# crossfire-20x20.net
KiCad netlist of a schematic drawn in EAGLE
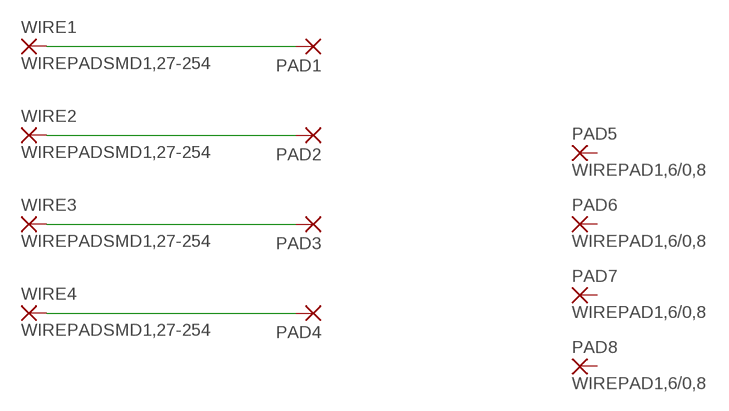
[diagram p0: schematic, sheet 1]

(export (version "E")
  (design (tool "Eeschema 10.0.6"))
  (components
    (comp (ref "PAD1")
      (value "1,6/0,8")
      (footprint "eagle-import:1,6_0,8")
      (libsource (lib "eagle-import") (part "1,6/0,8"))
    )
    (comp (ref "PAD2")
      (value "1,6/0,8")
      (footprint "eagle-import:1,6_0,8")
      (libsource (lib "eagle-import") (part "1,6/0,8"))
    )
    (comp (ref "PAD3")
      (value "1,6/0,8")
      (footprint "eagle-import:1,6_0,8")
      (libsource (lib "eagle-import") (part "1,6/0,8"))
    )
    (comp (ref "PAD4")
      (value "1,6/0,8")
      (footprint "eagle-import:1,6_0,8")
      (libsource (lib "eagle-import") (part "1,6/0,8"))
    )
    (comp (ref "PAD5")
      (value "WIREPAD1,6/0,8")
      (footprint "eagle-import:1,6_0,8")
      (libsource (lib "eagle-import") (part "WIREPAD1,6/0,8"))
    )
    (comp (ref "PAD6")
      (value "WIREPAD1,6/0,8")
      (footprint "eagle-import:1,6_0,8")
      (libsource (lib "eagle-import") (part "WIREPAD1,6/0,8"))
    )
    (comp (ref "PAD7")
      (value "WIREPAD1,6/0,8")
      (footprint "eagle-import:1,6_0,8")
      (libsource (lib "eagle-import") (part "WIREPAD1,6/0,8"))
    )
    (comp (ref "PAD8")
      (value "WIREPAD1,6/0,8")
      (footprint "eagle-import:1,6_0,8")
      (libsource (lib "eagle-import") (part "WIREPAD1,6/0,8"))
    )
    (comp (ref "WIRE1")
      (value "WIREPADSMD1,27-254")
      (footprint "eagle-import:SMD1,27-2,54")
      (libsource (lib "eagle-import") (part "WIREPADSMD1,27-254"))
    )
    (comp (ref "WIRE2")
      (value "WIREPADSMD1,27-254")
      (footprint "eagle-import:SMD1,27-2,54")
      (libsource (lib "eagle-import") (part "WIREPADSMD1,27-254"))
    )
    (comp (ref "WIRE3")
      (value "WIREPADSMD1,27-254")
      (footprint "eagle-import:SMD1,27-2,54")
      (libsource (lib "eagle-import") (part "WIREPADSMD1,27-254"))
    )
    (comp (ref "WIRE4")
      (value "WIREPADSMD1,27-254")
      (footprint "eagle-import:SMD1,27-2,54")
      (libsource (lib "eagle-import") (part "WIREPADSMD1,27-254"))
    )
  )
  (nets
    (net (code "1") (name "Net-(PAD1-P)") (class "Default")
      (node (ref "PAD1") (pin "1") (pinfunction "P_1") (pintype "passive"))
      (node (ref "WIRE1") (pin "1") (pinfunction "P_1") (pintype "passive"))
    )
    (net (code "2") (name "Net-(PAD2-P)") (class "Default")
      (node (ref "PAD2") (pin "1") (pinfunction "P_1") (pintype "passive"))
      (node (ref "WIRE2") (pin "1") (pinfunction "P_1") (pintype "passive"))
    )
    (net (code "3") (name "Net-(PAD3-P)") (class "Default")
      (node (ref "PAD3") (pin "1") (pinfunction "P_1") (pintype "passive"))
      (node (ref "WIRE3") (pin "1") (pinfunction "P_1") (pintype "passive"))
    )
    (net (code "4") (name "Net-(PAD4-P)") (class "Default")
      (node (ref "PAD4") (pin "1") (pinfunction "P_1") (pintype "passive"))
      (node (ref "WIRE4") (pin "1") (pinfunction "P_1") (pintype "passive"))
    )
    (net (code "5") (name "unconnected-(PAD5-P-Pad1)") (class "Default")
      (node (ref "PAD5") (pin "1") (pinfunction "P_1") (pintype "passive"))
    )
    (net (code "6") (name "unconnected-(PAD6-P-Pad1)") (class "Default")
      (node (ref "PAD6") (pin "1") (pinfunction "P_1") (pintype "passive"))
    )
    (net (code "7") (name "unconnected-(PAD7-P-Pad1)") (class "Default")
      (node (ref "PAD7") (pin "1") (pinfunction "P_1") (pintype "passive"))
    )
    (net (code "8") (name "unconnected-(PAD8-P-Pad1)") (class "Default")
      (node (ref "PAD8") (pin "1") (pinfunction "P_1") (pintype "passive"))
    )
  )
)
